# dsub_to_pins.net
KiCad netlist of a schematic drawn in EAGLE
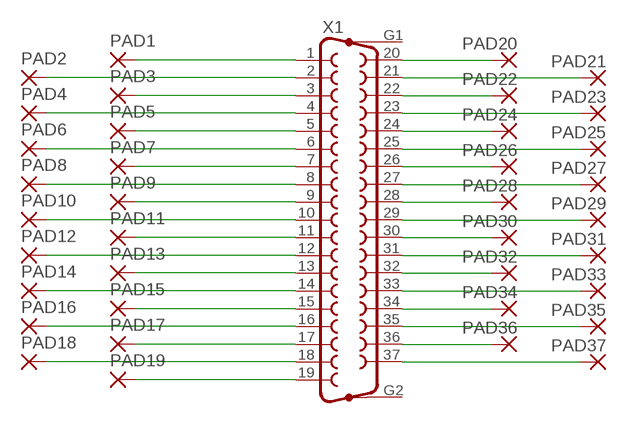
[diagram p0: schematic, sheet 1]

(export (version "E")
  (design (tool "Eeschema 10.0.6"))
  (components
    (comp (ref "PAD1")
      (value "WIREPAD3,81/1,3")
      (footprint "eagle-import:3,81_1,3")
      (libsource (lib "eagle-import") (part "WIREPAD3,81/1,3"))
    )
    (comp (ref "PAD2")
      (value "WIREPAD3,81/1,3")
      (footprint "eagle-import:3,81_1,3")
      (libsource (lib "eagle-import") (part "WIREPAD3,81/1,3"))
    )
    (comp (ref "PAD3")
      (value "WIREPAD3,81/1,3")
      (footprint "eagle-import:3,81_1,3")
      (libsource (lib "eagle-import") (part "WIREPAD3,81/1,3"))
    )
    (comp (ref "PAD4")
      (value "WIREPAD3,81/1,3")
      (footprint "eagle-import:3,81_1,3")
      (libsource (lib "eagle-import") (part "WIREPAD3,81/1,3"))
    )
    (comp (ref "PAD5")
      (value "WIREPAD3,81/1,3")
      (footprint "eagle-import:3,81_1,3")
      (libsource (lib "eagle-import") (part "WIREPAD3,81/1,3"))
    )
    (comp (ref "PAD6")
      (value "WIREPAD3,81/1,3")
      (footprint "eagle-import:3,81_1,3")
      (libsource (lib "eagle-import") (part "WIREPAD3,81/1,3"))
    )
    (comp (ref "PAD7")
      (value "WIREPAD3,81/1,3")
      (footprint "eagle-import:3,81_1,3")
      (libsource (lib "eagle-import") (part "WIREPAD3,81/1,3"))
    )
    (comp (ref "PAD8")
      (value "WIREPAD3,81/1,3")
      (footprint "eagle-import:3,81_1,3")
      (libsource (lib "eagle-import") (part "WIREPAD3,81/1,3"))
    )
    (comp (ref "PAD9")
      (value "WIREPAD3,81/1,3")
      (footprint "eagle-import:3,81_1,3")
      (libsource (lib "eagle-import") (part "WIREPAD3,81/1,3"))
    )
    (comp (ref "PAD10")
      (value "WIREPAD3,81/1,3")
      (footprint "eagle-import:3,81_1,3")
      (libsource (lib "eagle-import") (part "WIREPAD3,81/1,3"))
    )
    (comp (ref "PAD11")
      (value "WIREPAD3,81/1,3")
      (footprint "eagle-import:3,81_1,3")
      (libsource (lib "eagle-import") (part "WIREPAD3,81/1,3"))
    )
    (comp (ref "PAD12")
      (value "WIREPAD3,81/1,3")
      (footprint "eagle-import:3,81_1,3")
      (libsource (lib "eagle-import") (part "WIREPAD3,81/1,3"))
    )
    (comp (ref "PAD13")
      (value "WIREPAD3,81/1,3")
      (footprint "eagle-import:3,81_1,3")
      (libsource (lib "eagle-import") (part "WIREPAD3,81/1,3"))
    )
    (comp (ref "PAD14")
      (value "WIREPAD3,81/1,3")
      (footprint "eagle-import:3,81_1,3")
      (libsource (lib "eagle-import") (part "WIREPAD3,81/1,3"))
    )
    (comp (ref "PAD15")
      (value "WIREPAD3,81/1,3")
      (footprint "eagle-import:3,81_1,3")
      (libsource (lib "eagle-import") (part "WIREPAD3,81/1,3"))
    )
    (comp (ref "PAD16")
      (value "WIREPAD3,81/1,3")
      (footprint "eagle-import:3,81_1,3")
      (libsource (lib "eagle-import") (part "WIREPAD3,81/1,3"))
    )
    (comp (ref "PAD17")
      (value "WIREPAD3,81/1,3")
      (footprint "eagle-import:3,81_1,3")
      (libsource (lib "eagle-import") (part "WIREPAD3,81/1,3"))
    )
    (comp (ref "PAD18")
      (value "WIREPAD3,81/1,3")
      (footprint "eagle-import:3,81_1,3")
      (libsource (lib "eagle-import") (part "WIREPAD3,81/1,3"))
    )
    (comp (ref "PAD19")
      (value "WIREPAD3,81/1,3")
      (footprint "eagle-import:3,81_1,3")
      (libsource (lib "eagle-import") (part "WIREPAD3,81/1,3"))
    )
    (comp (ref "PAD20")
      (value "WIREPAD3,81/1,3")
      (footprint "eagle-import:3,81_1,3")
      (libsource (lib "eagle-import") (part "WIREPAD3,81/1,3"))
    )
    (comp (ref "PAD21")
      (value "WIREPAD3,81/1,3")
      (footprint "eagle-import:3,81_1,3")
      (libsource (lib "eagle-import") (part "WIREPAD3,81/1,3"))
    )
    (comp (ref "PAD22")
      (value "WIREPAD3,81/1,3")
      (footprint "eagle-import:3,81_1,3")
      (libsource (lib "eagle-import") (part "WIREPAD3,81/1,3"))
    )
    (comp (ref "PAD23")
      (value "WIREPAD3,81/1,3")
      (footprint "eagle-import:3,81_1,3")
      (libsource (lib "eagle-import") (part "WIREPAD3,81/1,3"))
    )
    (comp (ref "PAD24")
      (value "WIREPAD3,81/1,3")
      (footprint "eagle-import:3,81_1,3")
      (libsource (lib "eagle-import") (part "WIREPAD3,81/1,3"))
    )
    (comp (ref "PAD25")
      (value "WIREPAD3,81/1,3")
      (footprint "eagle-import:3,81_1,3")
      (libsource (lib "eagle-import") (part "WIREPAD3,81/1,3"))
    )
    (comp (ref "PAD26")
      (value "WIREPAD3,81/1,3")
      (footprint "eagle-import:3,81_1,3")
      (libsource (lib "eagle-import") (part "WIREPAD3,81/1,3"))
    )
    (comp (ref "PAD27")
      (value "WIREPAD3,81/1,3")
      (footprint "eagle-import:3,81_1,3")
      (libsource (lib "eagle-import") (part "WIREPAD3,81/1,3"))
    )
    (comp (ref "PAD28")
      (value "WIREPAD3,81/1,3")
      (footprint "eagle-import:3,81_1,3")
      (libsource (lib "eagle-import") (part "WIREPAD3,81/1,3"))
    )
    (comp (ref "PAD29")
      (value "WIREPAD3,81/1,3")
      (footprint "eagle-import:3,81_1,3")
      (libsource (lib "eagle-import") (part "WIREPAD3,81/1,3"))
    )
    (comp (ref "PAD30")
      (value "WIREPAD3,81/1,3")
      (footprint "eagle-import:3,81_1,3")
      (libsource (lib "eagle-import") (part "WIREPAD3,81/1,3"))
    )
    (comp (ref "PAD31")
      (value "WIREPAD3,81/1,3")
      (footprint "eagle-import:3,81_1,3")
      (libsource (lib "eagle-import") (part "WIREPAD3,81/1,3"))
    )
    (comp (ref "PAD32")
      (value "WIREPAD3,81/1,3")
      (footprint "eagle-import:3,81_1,3")
      (libsource (lib "eagle-import") (part "WIREPAD3,81/1,3"))
    )
    (comp (ref "PAD33")
      (value "WIREPAD3,81/1,3")
      (footprint "eagle-import:3,81_1,3")
      (libsource (lib "eagle-import") (part "WIREPAD3,81/1,3"))
    )
    (comp (ref "PAD34")
      (value "WIREPAD3,81/1,3")
      (footprint "eagle-import:3,81_1,3")
      (libsource (lib "eagle-import") (part "WIREPAD3,81/1,3"))
    )
    (comp (ref "PAD35")
      (value "WIREPAD3,81/1,3")
      (footprint "eagle-import:3,81_1,3")
      (libsource (lib "eagle-import") (part "WIREPAD3,81/1,3"))
    )
    (comp (ref "PAD36")
      (value "WIREPAD3,81/1,3")
      (footprint "eagle-import:3,81_1,3")
      (libsource (lib "eagle-import") (part "WIREPAD3,81/1,3"))
    )
    (comp (ref "PAD37")
      (value "WIREPAD3,81/1,3")
      (footprint "eagle-import:3,81_1,3")
      (libsource (lib "eagle-import") (part "WIREPAD3,81/1,3"))
    )
    (comp (ref "X1")
      (value "F37HP")
      (footprint "eagle-import:F37HP")
      (libsource (lib "eagle-import") (part "F37HP"))
    )
  )
  (nets
    (net (code "1") (name "Net-(PAD1-P)") (class "Default")
      (node (ref "PAD1") (pin "1") (pinfunction "P_1") (pintype "passive"))
      (node (ref "X1") (pin "1") (pinfunction "1_1") (pintype "passive"))
    )
    (net (code "2") (name "Net-(PAD2-P)") (class "Default")
      (node (ref "PAD2") (pin "1") (pinfunction "P_1") (pintype "passive"))
      (node (ref "X1") (pin "2") (pinfunction "2_2") (pintype "passive"))
    )
    (net (code "3") (name "Net-(PAD3-P)") (class "Default")
      (node (ref "PAD3") (pin "1") (pinfunction "P_1") (pintype "passive"))
      (node (ref "X1") (pin "3") (pinfunction "3_3") (pintype "passive"))
    )
    (net (code "4") (name "Net-(PAD4-P)") (class "Default")
      (node (ref "PAD4") (pin "1") (pinfunction "P_1") (pintype "passive"))
      (node (ref "X1") (pin "4") (pinfunction "4_4") (pintype "passive"))
    )
    (net (code "5") (name "Net-(PAD5-P)") (class "Default")
      (node (ref "PAD5") (pin "1") (pinfunction "P_1") (pintype "passive"))
      (node (ref "X1") (pin "5") (pinfunction "5_5") (pintype "passive"))
    )
    (net (code "6") (name "Net-(PAD6-P)") (class "Default")
      (node (ref "PAD6") (pin "1") (pinfunction "P_1") (pintype "passive"))
      (node (ref "X1") (pin "6") (pinfunction "6_6") (pintype "passive"))
    )
    (net (code "7") (name "Net-(PAD7-P)") (class "Default")
      (node (ref "PAD7") (pin "1") (pinfunction "P_1") (pintype "passive"))
      (node (ref "X1") (pin "7") (pinfunction "7_7") (pintype "passive"))
    )
    (net (code "8") (name "Net-(PAD8-P)") (class "Default")
      (node (ref "PAD8") (pin "1") (pinfunction "P_1") (pintype "passive"))
      (node (ref "X1") (pin "8") (pinfunction "8_8") (pintype "passive"))
    )
    (net (code "9") (name "Net-(PAD9-P)") (class "Default")
      (node (ref "PAD9") (pin "1") (pinfunction "P_1") (pintype "passive"))
      (node (ref "X1") (pin "9") (pinfunction "9_9") (pintype "passive"))
    )
    (net (code "10") (name "Net-(PAD10-P)") (class "Default")
      (node (ref "PAD10") (pin "1") (pinfunction "P_1") (pintype "passive"))
      (node (ref "X1") (pin "10") (pinfunction "10_10") (pintype "passive"))
    )
    (net (code "11") (name "Net-(PAD11-P)") (class "Default")
      (node (ref "PAD11") (pin "1") (pinfunction "P_1") (pintype "passive"))
      (node (ref "X1") (pin "11") (pinfunction "11_11") (pintype "passive"))
    )
    (net (code "12") (name "Net-(PAD12-P)") (class "Default")
      (node (ref "PAD12") (pin "1") (pinfunction "P_1") (pintype "passive"))
      (node (ref "X1") (pin "12") (pinfunction "12_12") (pintype "passive"))
    )
    (net (code "13") (name "Net-(PAD13-P)") (class "Default")
      (node (ref "PAD13") (pin "1") (pinfunction "P_1") (pintype "passive"))
      (node (ref "X1") (pin "13") (pinfunction "13_13") (pintype "passive"))
    )
    (net (code "14") (name "Net-(PAD14-P)") (class "Default")
      (node (ref "PAD14") (pin "1") (pinfunction "P_1") (pintype "passive"))
      (node (ref "X1") (pin "14") (pinfunction "14_14") (pintype "passive"))
    )
    (net (code "15") (name "Net-(PAD15-P)") (class "Default")
      (node (ref "PAD15") (pin "1") (pinfunction "P_1") (pintype "passive"))
      (node (ref "X1") (pin "15") (pinfunction "15_15") (pintype "passive"))
    )
    (net (code "16") (name "Net-(PAD16-P)") (class "Default")
      (node (ref "PAD16") (pin "1") (pinfunction "P_1") (pintype "passive"))
      (node (ref "X1") (pin "16") (pinfunction "16_16") (pintype "passive"))
    )
    (net (code "17") (name "Net-(PAD17-P)") (class "Default")
      (node (ref "PAD17") (pin "1") (pinfunction "P_1") (pintype "passive"))
      (node (ref "X1") (pin "17") (pinfunction "17_17") (pintype "passive"))
    )
    (net (code "18") (name "Net-(PAD18-P)") (class "Default")
      (node (ref "PAD18") (pin "1") (pinfunction "P_1") (pintype "passive"))
      (node (ref "X1") (pin "18") (pinfunction "18_18") (pintype "passive"))
    )
    (net (code "19") (name "Net-(PAD19-P)") (class "Default")
      (node (ref "PAD19") (pin "1") (pinfunction "P_1") (pintype "passive"))
      (node (ref "X1") (pin "19") (pinfunction "19_19") (pintype "passive"))
    )
    (net (code "20") (name "Net-(PAD20-P)") (class "Default")
      (node (ref "PAD20") (pin "1") (pinfunction "P_1") (pintype "passive"))
      (node (ref "X1") (pin "20") (pinfunction "20_20") (pintype "passive"))
    )
    (net (code "21") (name "Net-(PAD21-P)") (class "Default")
      (node (ref "PAD21") (pin "1") (pinfunction "P_1") (pintype "passive"))
      (node (ref "X1") (pin "21") (pinfunction "21_21") (pintype "passive"))
    )
    (net (code "22") (name "Net-(PAD22-P)") (class "Default")
      (node (ref "PAD22") (pin "1") (pinfunction "P_1") (pintype "passive"))
      (node (ref "X1") (pin "22") (pinfunction "22_22") (pintype "passive"))
    )
    (net (code "23") (name "Net-(PAD23-P)") (class "Default")
      (node (ref "PAD23") (pin "1") (pinfunction "P_1") (pintype "passive"))
      (node (ref "X1") (pin "23") (pinfunction "23_23") (pintype "passive"))
    )
    (net (code "24") (name "Net-(PAD24-P)") (class "Default")
      (node (ref "PAD24") (pin "1") (pinfunction "P_1") (pintype "passive"))
      (node (ref "X1") (pin "24") (pinfunction "24_24") (pintype "passive"))
    )
    (net (code "25") (name "Net-(PAD25-P)") (class "Default")
      (node (ref "PAD25") (pin "1") (pinfunction "P_1") (pintype "passive"))
      (node (ref "X1") (pin "25") (pinfunction "25_25") (pintype "passive"))
    )
    (net (code "26") (name "Net-(PAD26-P)") (class "Default")
      (node (ref "PAD26") (pin "1") (pinfunction "P_1") (pintype "passive"))
      (node (ref "X1") (pin "26") (pinfunction "26_26") (pintype "passive"))
    )
    (net (code "27") (name "Net-(PAD27-P)") (class "Default")
      (node (ref "PAD27") (pin "1") (pinfunction "P_1") (pintype "passive"))
      (node (ref "X1") (pin "27") (pinfunction "27_27") (pintype "passive"))
    )
    (net (code "28") (name "Net-(PAD28-P)") (class "Default")
      (node (ref "PAD28") (pin "1") (pinfunction "P_1") (pintype "passive"))
      (node (ref "X1") (pin "28") (pinfunction "28_28") (pintype "passive"))
    )
    (net (code "29") (name "Net-(PAD29-P)") (class "Default")
      (node (ref "PAD29") (pin "1") (pinfunction "P_1") (pintype "passive"))
      (node (ref "X1") (pin "29") (pinfunction "29_29") (pintype "passive"))
    )
    (net (code "30") (name "Net-(PAD30-P)") (class "Default")
      (node (ref "PAD30") (pin "1") (pinfunction "P_1") (pintype "passive"))
      (node (ref "X1") (pin "30") (pinfunction "30_30") (pintype "passive"))
    )
    (net (code "31") (name "Net-(PAD31-P)") (class "Default")
      (node (ref "PAD31") (pin "1") (pinfunction "P_1") (pintype "passive"))
      (node (ref "X1") (pin "31") (pinfunction "31_31") (pintype "passive"))
    )
    (net (code "32") (name "Net-(PAD32-P)") (class "Default")
      (node (ref "PAD32") (pin "1") (pinfunction "P_1") (pintype "passive"))
      (node (ref "X1") (pin "32") (pinfunction "32_32") (pintype "passive"))
    )
    (net (code "33") (name "Net-(PAD33-P)") (class "Default")
      (node (ref "PAD33") (pin "1") (pinfunction "P_1") (pintype "passive"))
      (node (ref "X1") (pin "33") (pinfunction "33_33") (pintype "passive"))
    )
    (net (code "34") (name "Net-(PAD34-P)") (class "Default")
      (node (ref "PAD34") (pin "1") (pinfunction "P_1") (pintype "passive"))
      (node (ref "X1") (pin "34") (pinfunction "34_34") (pintype "passive"))
    )
    (net (code "35") (name "Net-(PAD35-P)") (class "Default")
      (node (ref "PAD35") (pin "1") (pinfunction "P_1") (pintype "passive"))
      (node (ref "X1") (pin "35") (pinfunction "35_35") (pintype "passive"))
    )
    (net (code "36") (name "Net-(PAD36-P)") (class "Default")
      (node (ref "PAD36") (pin "1") (pinfunction "P_1") (pintype "passive"))
      (node (ref "X1") (pin "36") (pinfunction "36_36") (pintype "passive"))
    )
    (net (code "37") (name "Net-(PAD37-P)") (class "Default")
      (node (ref "PAD37") (pin "1") (pinfunction "P_1") (pintype "passive"))
      (node (ref "X1") (pin "37") (pinfunction "37_37") (pintype "passive"))
    )
    (net (code "38") (name "unconnected-(X1-PadG1)") (class "Default")
      (node (ref "X1") (pin "G1") (pinfunction "G1_G1") (pintype "passive"))
    )
    (net (code "39") (name "unconnected-(X1-PadG2)") (class "Default")
      (node (ref "X1") (pin "G2") (pinfunction "G2_G2") (pintype "passive"))
    )
  )
)
